# RS232.net
KiCad netlist of a schematic drawn in EasyEDA Pro
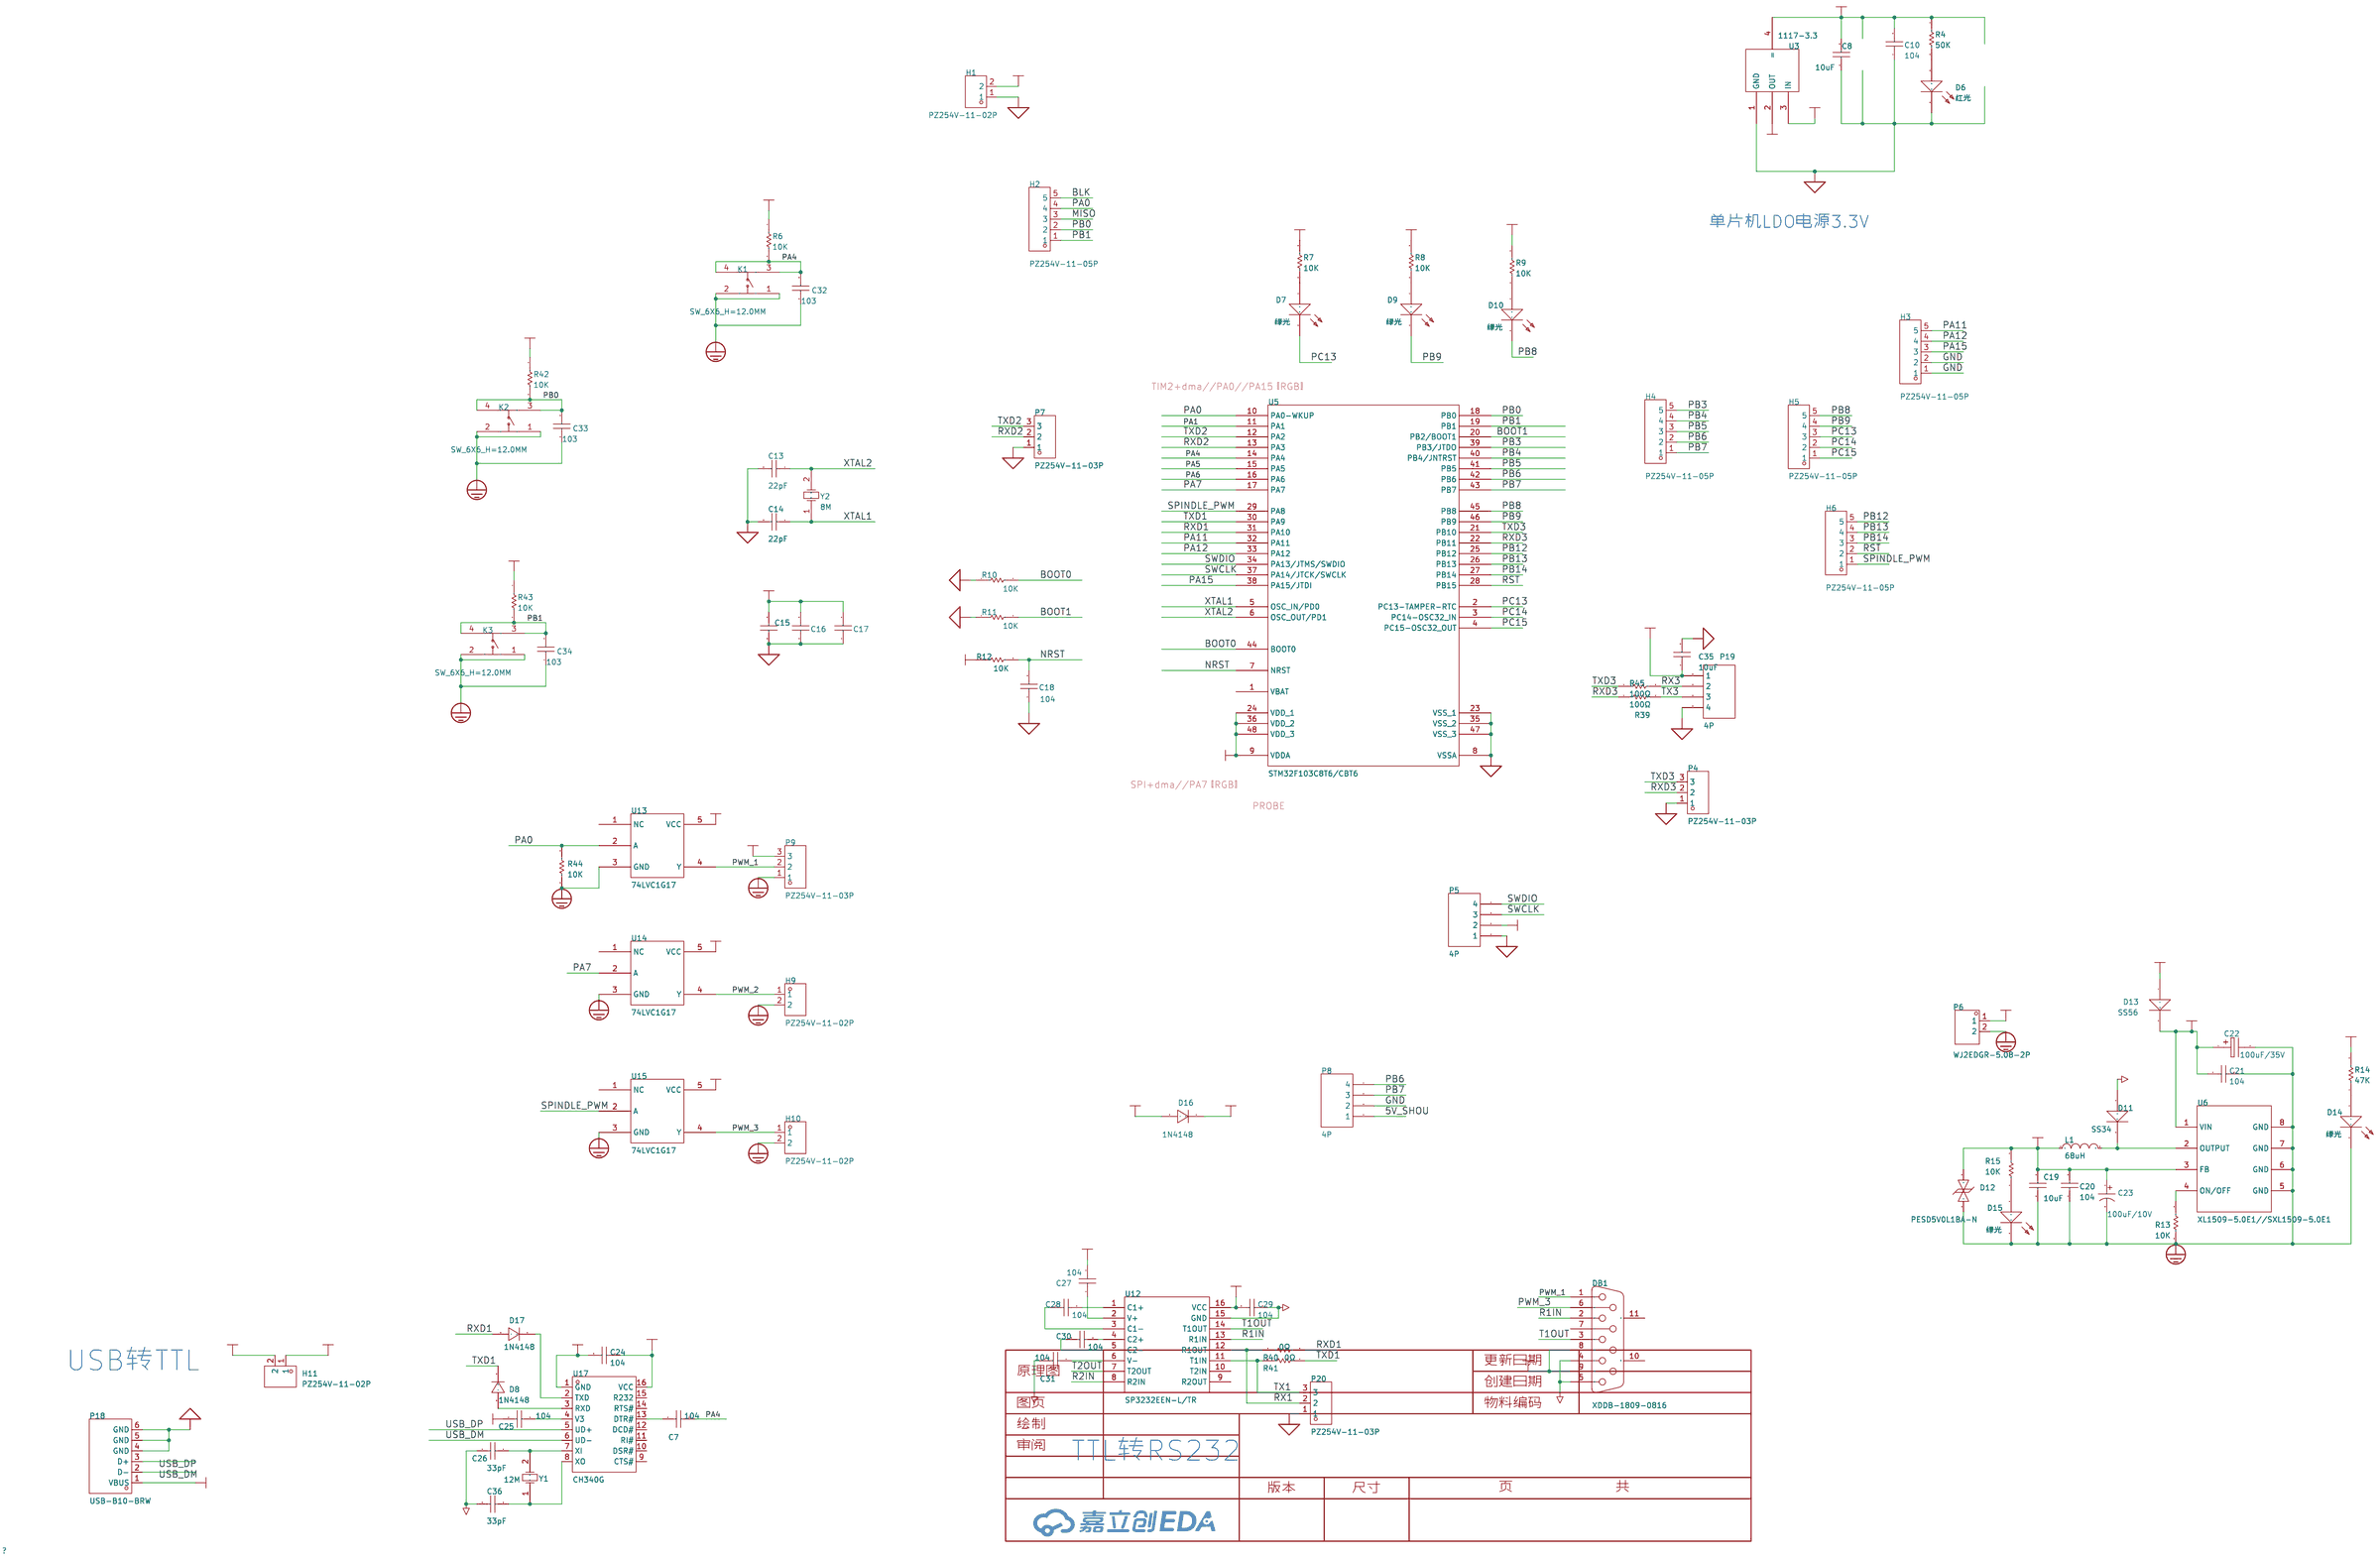
[diagram p0: schematic sheet]

(export (version "E")
  (design (tool "Eeschema 10.0.6"))
  (components
    (comp (ref "C7")
      (value "104")
      (footprint "easyedapro:0603C")
      (description "Capacitor (Semiconductor SIM Model)")
      (libsource (lib "easyedapro") (part "Cap Semi"))
    )
    (comp (ref "C8") (value "10uF") (libsource (lib "") (part "CAP_1")))
    (comp (ref "C10")
      (value "104")
      (footprint "easyedapro:0603C")
      (description "Capacitor (Semiconductor SIM Model)")
      (libsource (lib "easyedapro") (part "Cap Semi"))
    )
    (comp (ref "C13")
      (value "100pF")
      (footprint "easyedapro:0603C")
      (description "Capacitor (Semiconductor SIM Model)")
      (libsource (lib "easyedapro") (part "Cap Semi"))
    )
    (comp (ref "C14")
      (value "100pF")
      (footprint "easyedapro:0603C")
      (description "Capacitor (Semiconductor SIM Model)")
      (libsource (lib "easyedapro") (part "Cap Semi"))
    )
    (comp (ref "C15")
      (value "104")
      (footprint "easyedapro:电解电容贴片6X6")
      (libsource (lib "easyedapro") (part "CAP"))
    )
    (comp (ref "C16")
      (value "104")
      (footprint "easyedapro:电解电容贴片6X6")
      (libsource (lib "easyedapro") (part "CAP"))
    )
    (comp (ref "C17")
      (value "104")
      (footprint "easyedapro:电解电容贴片6X6")
      (libsource (lib "easyedapro") (part "CAP"))
    )
    (comp (ref "C18")
      (value "104")
      (footprint "easyedapro:0603C")
      (description "Capacitor (Semiconductor SIM Model)")
      (libsource (lib "easyedapro") (part "Cap Semi"))
    )
    (comp (ref "C19") (value "10uF") (libsource (lib "") (part "CAP_1")))
    (comp (ref "C20")
      (value "104")
      (footprint "easyedapro:0603C")
      (description "Capacitor (Semiconductor SIM Model)")
      (libsource (lib "easyedapro") (part "Cap Semi"))
    )
    (comp (ref "C21")
      (value "104")
      (footprint "easyedapro:0603C")
      (description "Capacitor (Semiconductor SIM Model)")
      (libsource (lib "easyedapro") (part "Cap Semi"))
    )
    (comp (ref "C22")
      (value "100uF/35V")
      (footprint "easyedapro:电解电容贴片10x10")
      (libsource (lib "easyedapro") (part "ELECTRO1"))
    )
    (comp (ref "C23")
      (value "100uF/10V")
      (footprint "easyedapro:CAP-SMD_BD5.0-L5.3-W5.3-RD")
      (fields (field (name "Manufacturer Part") "CS1A101M-CRD54") (field (name "Manufacturer") "ST(先科)"))
      (libsource (lib "easyedapro") (part "CS1A101M-CRD54"))
    )
    (comp (ref "C24")
      (value "104")
      (footprint "easyedapro:0603C")
      (description "Capacitor (Semiconductor SIM Model)")
      (libsource (lib "easyedapro") (part "Cap Semi"))
    )
    (comp (ref "C25")
      (value "104")
      (footprint "easyedapro:0603C")
      (description "Capacitor (Semiconductor SIM Model)")
      (libsource (lib "easyedapro") (part "Cap Semi"))
    )
    (comp (ref "C26")
      (value "18pF")
      (footprint "easyedapro:0603C")
      (description "Capacitor (Semiconductor SIM Model)")
      (libsource (lib "easyedapro") (part "Cap Semi"))
    )
    (comp (ref "C27")
      (value "104")
      (footprint "easyedapro:0603C")
      (description "Capacitor (Semiconductor SIM Model)")
      (libsource (lib "easyedapro") (part "Cap Semi"))
    )
    (comp (ref "C28")
      (value "104")
      (footprint "easyedapro:0603C")
      (description "Capacitor (Semiconductor SIM Model)")
      (libsource (lib "easyedapro") (part "Cap Semi"))
    )
    (comp (ref "C29")
      (value "104")
      (footprint "easyedapro:0603C")
      (description "Capacitor (Semiconductor SIM Model)")
      (libsource (lib "easyedapro") (part "Cap Semi"))
    )
    (comp (ref "C30")
      (value "104")
      (footprint "easyedapro:0603C")
      (description "Capacitor (Semiconductor SIM Model)")
      (libsource (lib "easyedapro") (part "Cap Semi"))
    )
    (comp (ref "C31")
      (value "104")
      (footprint "easyedapro:0603C")
      (description "Capacitor (Semiconductor SIM Model)")
      (libsource (lib "easyedapro") (part "Cap Semi"))
    )
    (comp (ref "C32") (value "103") (footprint "easyedapro:11") (libsource (lib "easyedapro") (part "CAP")))
    (comp (ref "C33") (value "103") (footprint "easyedapro:11") (libsource (lib "easyedapro") (part "CAP")))
    (comp (ref "C34") (value "103") (footprint "easyedapro:11") (libsource (lib "easyedapro") (part "CAP")))
    (comp (ref "C35") (value "10uF") (libsource (lib "") (part "CAP_1")))
    (comp (ref "C36")
      (value "18pF")
      (footprint "easyedapro:0603C")
      (description "Capacitor (Semiconductor SIM Model)")
      (libsource (lib "easyedapro") (part "Cap Semi"))
    )
    (comp (ref "D6")
      (value "红光")
      (footprint "easyedapro:0603LED")
      (libsource (lib "easyedapro") (part "LED"))
    )
    (comp (ref "D7")
      (value "绿光")
      (footprint "easyedapro:0603LED")
      (libsource (lib "easyedapro") (part "LED"))
    )
    (comp (ref "D8")
      (value "1N4148")
      (footprint "easyedapro:SOD-123_L2.8-W1.8-LS3.7-RD")
      (fields (field (name "Manufacturer") "MCC(美微科)"))
      (libsource (lib "easyedapro") (part "1N4148W-TP"))
    )
    (comp (ref "D9")
      (value "绿光")
      (footprint "easyedapro:0603LED")
      (libsource (lib "easyedapro") (part "LED"))
    )
    (comp (ref "D10")
      (value "绿光")
      (footprint "easyedapro:0603LED")
      (libsource (lib "easyedapro") (part "LED"))
    )
    (comp (ref "D11") (value "SS34") (libsource (lib "easyedapro") (part "1N4148")))
    (comp (ref "D12")
      (value "PESD5V0L1BA-N")
      (footprint "easyedapro:SOD-523_L1.2-W0.8-LS1.6-BI")
      (description "极性:Bidirectional;反向关断电压（典型值）:5V (Max);击穿电压（最小值）:6V;箝位电压:15V;峰值脉冲电流（10/1000us）:5A (8/20us);")
      (fields (field (name "Manufacturer") "BORN伯恩半导体"))
      (libsource (lib "easyedapro") (part "PESD5V0S1BBN"))
    )
    (comp (ref "D13") (value "SS56") (footprint "easyedapro:SMA") (libsource (lib "") (part "1N4148_1")))
    (comp (ref "D14")
      (value "绿光")
      (footprint "easyedapro:0603LED")
      (libsource (lib "easyedapro") (part "LED"))
    )
    (comp (ref "D15")
      (value "绿光")
      (footprint "easyedapro:0603LED")
      (libsource (lib "easyedapro") (part "LED"))
    )
    (comp (ref "D16")
      (value "1N4148")
      (footprint "easyedapro:SOD-123_L2.8-W1.8-LS3.7-RD")
      (fields (field (name "Manufacturer") "MCC(美微科)"))
      (libsource (lib "easyedapro") (part "1N4148W-TP"))
    )
    (comp (ref "D17")
      (value "1N4148")
      (footprint "easyedapro:SOD-123_L2.8-W1.8-LS3.7-RD")
      (fields (field (name "Manufacturer") "MCC(美微科)"))
      (libsource (lib "easyedapro") (part "1N4148W-TP"))
    )
    (comp (ref "DB1")
      (value "XDDB-1809-0816")
      (footprint "easyedapro:DB9-TH_LD09P33E4GV00LF")
      (description "连接器类型:常规D-Sub;公母:公;总PIN位数:9P;安装方式:弯插;排数:2;额定电流-信号脚:3A;工作温度范围:-40°C~+85°C;")
      (fields (field (name "Manufacturer") "LX(连欣科技)"))
      (libsource (lib "easyedapro") (part "XDDB-1809-0816"))
    )
    (comp (ref "H1")
      (value "PZ254V-11-02P")
      (footprint "easyedapro:HDR-TH_2P-P2.54-V-M")
      (fields (field (name "Manufacturer") "XFCN(兴飞)"))
      (libsource (lib "easyedapro") (part "PZ254V-11-02P"))
    )
    (comp (ref "H2")
      (value "PZ254V-11-05P")
      (footprint "easyedapro:HDR-TH_5P-P2.54-V-M")
      (fields (field (name "Manufacturer") "XFCN(兴飞)"))
      (libsource (lib "easyedapro") (part "PZ254V-11-05P"))
    )
    (comp (ref "H3")
      (value "PZ254V-11-05P")
      (footprint "easyedapro:HDR-TH_5P-P2.54-V-M")
      (fields (field (name "Manufacturer") "XFCN(兴飞)"))
      (libsource (lib "easyedapro") (part "PZ254V-11-05P"))
    )
    (comp (ref "H4")
      (value "PZ254V-11-05P")
      (footprint "easyedapro:HDR-TH_5P-P2.54-V-M")
      (fields (field (name "Manufacturer") "XFCN(兴飞)"))
      (libsource (lib "easyedapro") (part "PZ254V-11-05P"))
    )
    (comp (ref "H5")
      (value "PZ254V-11-05P")
      (footprint "easyedapro:HDR-TH_5P-P2.54-V-M")
      (fields (field (name "Manufacturer") "XFCN(兴飞)"))
      (libsource (lib "easyedapro") (part "PZ254V-11-05P"))
    )
    (comp (ref "H6")
      (value "PZ254V-11-05P")
      (footprint "easyedapro:HDR-TH_5P-P2.54-V-M")
      (fields (field (name "Manufacturer") "XFCN(兴飞)"))
      (libsource (lib "easyedapro") (part "PZ254V-11-05P"))
    )
    (comp (ref "H9")
      (value "PZ254V-11-02P")
      (footprint "easyedapro:HDR-TH_2P-P2.54-V-M")
      (fields (field (name "Manufacturer") "XFCN(兴飞)"))
      (libsource (lib "easyedapro") (part "PZ254V-11-02P"))
    )
    (comp (ref "H10")
      (value "PZ254V-11-02P")
      (footprint "easyedapro:HDR-TH_2P-P2.54-V-M")
      (fields (field (name "Manufacturer") "XFCN(兴飞)"))
      (libsource (lib "easyedapro") (part "PZ254V-11-02P"))
    )
    (comp (ref "H11")
      (value "PZ254V-11-02P")
      (footprint "easyedapro:HDR-TH_2P-P2.54-V-M")
      (fields (field (name "Manufacturer") "XFCN(兴飞)"))
      (libsource (lib "easyedapro") (part "PZ254V-11-02P"))
    )
    (comp (ref "K1")
      (value "SW_6X6_H=12.0MM")
      (footprint "easyedapro:KEY-SMD_4P-L6.0-W6.0-P4.50-LS9.0")
      (libsource (lib "easyedapro") (part "SW_6X6_H=12.0MM"))
    )
    (comp (ref "K2")
      (value "SW_6X6_H=12.0MM")
      (footprint "easyedapro:KEY-SMD_4P-L6.0-W6.0-P4.50-LS9.0")
      (libsource (lib "easyedapro") (part "SW_6X6_H=12.0MM"))
    )
    (comp (ref "K3")
      (value "SW_6X6_H=12.0MM")
      (footprint "easyedapro:KEY-SMD_4P-L6.0-W6.0-P4.50-LS9.0")
      (libsource (lib "easyedapro") (part "SW_6X6_H=12.0MM"))
    )
    (comp (ref "L1")
      (value "68uH")
      (footprint "easyedapro:IND-SMD_L7.0-W7.0_SMDRI74-330MT")
      (description "电感值:33uH;精度:±20%;额定电流:960mA;饱和电流(Isat):1.8A;类型:屏蔽电感;")
      (fields (field (name "Manufacturer Part") "SMDRI74-330MT") (field (name "Manufacturer") "SXN(顺翔诺)"))
      (libsource (lib "easyedapro") (part "SMDRI74-330MT"))
    )
    (comp (ref "P4")
      (value "PZ254V-11-03P")
      (footprint "easyedapro:HDR-TH_3P-P2.54-V-M")
      (fields (field (name "Manufacturer") "XFCN(兴飞)"))
      (libsource (lib "easyedapro") (part "PZ254V-11-03P_C2937625"))
    )
    (comp (ref "P5") (value "4P") (libsource (lib "easyedapro") (part "4P")))
    (comp (ref "P6")
      (value "WJ2EDGR-5.08-2P")
      (footprint "easyedapro:CONN-TH_WJ2EDGR-5.08-2P")
      (description "每排PIN数:2;安装方式:弯针;排数:1;间距:5.08mm;连接器类型:板端/插座-开口;")
      (fields (field (name "Manufacturer") "KANGNEX(康奈克斯电气)"))
      (libsource (lib "easyedapro") (part "WJ2EDGR-5.08-2P"))
    )
    (comp (ref "P7")
      (value "PZ254V-11-03P")
      (footprint "easyedapro:HDR-TH_3P-P2.54-V-M")
      (fields (field (name "Manufacturer") "XFCN(兴飞)"))
      (libsource (lib "easyedapro") (part "PZ254V-11-03P_C2937625"))
    )
    (comp (ref "P8") (value "4P") (libsource (lib "easyedapro") (part "4P")))
    (comp (ref "P9")
      (value "PZ254V-11-03P")
      (footprint "easyedapro:HDR-TH_3P-P2.54-V-M")
      (fields (field (name "Manufacturer") "XFCN(兴飞)"))
      (libsource (lib "easyedapro") (part "PZ254V-11-03P_C2937625"))
    )
    (comp (ref "P18")
      (value "USB-B10-BRW")
      (footprint "easyedapro:USB-B-TH_USB-B10-BRW")
      (fields (field (name "Manufacturer") "XUNPU(讯普)"))
      (libsource (lib "easyedapro") (part "USB-B10-BRW"))
    )
    (comp (ref "P19") (value "4P") (footprint "easyedapro:HDR1X4_CON") (libsource (lib "") (part "4P_1")))
    (comp (ref "P20")
      (value "PZ254V-11-03P")
      (footprint "easyedapro:HDR-TH_3P-P2.54-V-M")
      (fields (field (name "Manufacturer") "XFCN(兴飞)"))
      (libsource (lib "easyedapro") (part "PZ254V-11-03P_C2937625"))
    )
    (comp (ref "R4")
      (value "50K")
      (footprint "easyedapro:0603R")
      (description "Resistor")
      (libsource (lib "easyedapro") (part "RES"))
    )
    (comp (ref "R6")
      (value "10K")
      (footprint "easyedapro:0603R")
      (description "Resistor")
      (libsource (lib "easyedapro") (part "RES"))
    )
    (comp (ref "R7")
      (value "10K")
      (footprint "easyedapro:0603R")
      (description "Resistor")
      (libsource (lib "easyedapro") (part "RES"))
    )
    (comp (ref "R8")
      (value "10K")
      (footprint "easyedapro:0603R")
      (description "Resistor")
      (libsource (lib "easyedapro") (part "RES"))
    )
    (comp (ref "R9")
      (value "10K")
      (footprint "easyedapro:0603R")
      (description "Resistor")
      (libsource (lib "easyedapro") (part "RES"))
    )
    (comp (ref "R10")
      (value "10K")
      (footprint "easyedapro:0603R")
      (description "Resistor")
      (libsource (lib "easyedapro") (part "RES"))
    )
    (comp (ref "R11")
      (value "10K")
      (footprint "easyedapro:0603R")
      (description "Resistor")
      (libsource (lib "easyedapro") (part "RES"))
    )
    (comp (ref "R12")
      (value "10K")
      (footprint "easyedapro:0603R")
      (description "Resistor")
      (libsource (lib "easyedapro") (part "RES"))
    )
    (comp (ref "R13")
      (value "10K")
      (footprint "easyedapro:0603R")
      (description "Resistor")
      (libsource (lib "easyedapro") (part "RES"))
    )
    (comp (ref "R14")
      (value "47K")
      (footprint "easyedapro:0603R")
      (description "Resistor")
      (libsource (lib "easyedapro") (part "RES"))
    )
    (comp (ref "R15")
      (value "10K")
      (footprint "easyedapro:0603R")
      (description "Resistor")
      (libsource (lib "easyedapro") (part "RES"))
    )
    (comp (ref "R39")
      (value "100Ω")
      (description "Resistor")
      (fields (field (name "Publisher") "Altium Limited"))
      (libsource (lib "") (part "RES_1"))
    )
    (comp (ref "R40")
      (value "0Ω")
      (footprint "easyedapro:0603R")
      (description "Resistor")
      (libsource (lib "easyedapro") (part "RES"))
    )
    (comp (ref "R41")
      (value "0Ω")
      (footprint "easyedapro:0603R")
      (description "Resistor")
      (libsource (lib "easyedapro") (part "RES"))
    )
    (comp (ref "R42")
      (value "10K")
      (footprint "easyedapro:0603R")
      (description "Resistor")
      (libsource (lib "easyedapro") (part "RES"))
    )
    (comp (ref "R43")
      (value "10K")
      (footprint "easyedapro:0603R")
      (description "Resistor")
      (libsource (lib "easyedapro") (part "RES"))
    )
    (comp (ref "R44")
      (value "10K")
      (footprint "easyedapro:0603R")
      (description "Resistor")
      (libsource (lib "easyedapro") (part "RES"))
    )
    (comp (ref "R45")
      (value "100Ω")
      (description "Resistor")
      (fields (field (name "Publisher") "Altium Limited"))
      (libsource (lib "") (part "RES_1"))
    )
    (comp (ref "U3")
      (value "1117-3.3")
      (footprint "easyedapro:SOT-223")
      (libsource (lib "easyedapro") (part "LM1117"))
    )
    (comp (ref "U5")
      (value "STM32F103C8T6/CBT6")
      (footprint "easyedapro:LQFP48")
      (description "STM32 ARM-based 32-bit MCU with 32 Kbytes Flash, 48-pin LQFP, Industrial Temperature")
      (libsource (lib "easyedapro") (part "STM32F103C6T6"))
    )
    (comp (ref "U6")
      (value "XL1509-5.0E1//SXL1509-5.0E1")
      (footprint "easyedapro:SOIC-8_L5.0-W4.0-P1.27-LS6.0-BL")
      (description "功能类型:降压型;同步整流:-;输出通道数:-;拓扑结构:-;输入电压:-;输出电流(最大值):-;开关频率:-;")
      (fields (field (name "Manufacturer") "XLSEMI(芯龙)"))
      (libsource (lib "easyedapro") (part "XL1509-5.0E1"))
    )
    (comp (ref "U12")
      (value "SP3232EEN-L/TR")
      (footprint "easyedapro:SOIC-16_L9.9-W3.9-P1.27-LS6.0-BL")
      (description "类型:收发器;数据速率:235Kbps;")
      (fields (field (name "Manufacturer") "MaxLinear(迈凌)"))
      (libsource (lib "easyedapro") (part "SP3232EEN-L/TR"))
    )
    (comp (ref "U13")
      (value "74LVC1G17")
      (footprint "easyedapro:SMD8")
      (libsource (lib "easyedapro") (part "74LVC1G04"))
    )
    (comp (ref "U14")
      (value "74LVC1G17")
      (footprint "easyedapro:SMD8")
      (libsource (lib "easyedapro") (part "74LVC1G04"))
    )
    (comp (ref "U15")
      (value "74LVC1G17")
      (footprint "easyedapro:SMD8")
      (libsource (lib "easyedapro") (part "74LVC1G04"))
    )
    (comp (ref "U17")
      (value "CH340G")
      (footprint "easyedapro:SOIC-16_L9.9-W3.9-P1.27-LS6.0-BL")
      (description "应用功能:收发器;接口协议:USB 2.0;数据速率:2Mbps;")
      (fields (field (name "Manufacturer") "WCH(南京沁恒)"))
      (libsource (lib "easyedapro") (part "CH340G"))
    )
    (comp (ref "Y1")
      (value "12M")
      (footprint "easyedapro:晶振贴片49SSMD")
      (description "Crystal Oscillator")
      (libsource (lib "easyedapro") (part "XTAL"))
    )
    (comp (ref "Y2")
      (value "8M")
      (footprint "easyedapro:晶振贴片49SSMD")
      (description "Crystal Oscillator")
      (libsource (lib "easyedapro") (part "XTAL"))
    )
  )
  (nets
    (net (code "1") (name "/BLK") (class "Default")
      (node (ref "H2") (pin "5") (pinfunction "5_5") (pintype "input"))
    )
    (net (code "2") (name "/BOOT0") (class "Default")
      (node (ref "R10") (pin "2") (pinfunction "2_2") (pintype "unspecified"))
      (node (ref "U5") (pin "44") (pinfunction "BOOT0_44") (pintype "input"))
    )
    (net (code "3") (name "/BOOT1") (class "Default")
      (node (ref "R11") (pin "2") (pinfunction "2_2") (pintype "unspecified"))
      (node (ref "U5") (pin "20") (pinfunction "PB2/BOOT1_20") (pintype "bidirectional"))
    )
    (net (code "4") (name "/MISO") (class "Default")
      (node (ref "H2") (pin "3") (pinfunction "3_3") (pintype "input"))
    )
    (net (code "5") (name "/NRST") (class "Default")
      (node (ref "C18") (pin "2") (pinfunction "2_2") (pintype "unspecified"))
      (node (ref "R12") (pin "2") (pinfunction "2_2") (pintype "unspecified"))
      (node (ref "U5") (pin "7") (pinfunction "NRST_7") (pintype "bidirectional"))
    )
    (net (code "6") (name "/PA0") (class "Default")
      (node (ref "H2") (pin "4") (pinfunction "4_4") (pintype "input"))
      (node (ref "R44") (pin "2") (pinfunction "2_2") (pintype "unspecified"))
      (node (ref "U13") (pin "2") (pinfunction "A_2") (pintype "unspecified"))
      (node (ref "U5") (pin "10") (pinfunction "PA0-WKUP_10") (pintype "bidirectional"))
    )
    (net (code "7") (name "/PA1") (class "Default")
      (node (ref "U5") (pin "11") (pinfunction "PA1_11") (pintype "bidirectional"))
    )
    (net (code "8") (name "/PA4") (class "Default")
      (node (ref "C32") (pin "2") (pinfunction "2_2") (pintype "unspecified"))
      (node (ref "C7") (pin "2") (pinfunction "2_2") (pintype "unspecified"))
      (node (ref "K1") (pin "3") (pinfunction "3_3") (pintype "unspecified"))
      (node (ref "K1") (pin "4") (pinfunction "4_4") (pintype "unspecified"))
      (node (ref "R6") (pin "2") (pinfunction "2_2") (pintype "unspecified"))
      (node (ref "U5") (pin "14") (pinfunction "PA4_14") (pintype "bidirectional"))
    )
    (net (code "9") (name "/PA5") (class "Default")
      (node (ref "U5") (pin "15") (pinfunction "PA5_15") (pintype "bidirectional"))
    )
    (net (code "10") (name "/PA6") (class "Default")
      (node (ref "U5") (pin "16") (pinfunction "PA6_16") (pintype "bidirectional"))
    )
    (net (code "11") (name "/PA7") (class "Default")
      (node (ref "U14") (pin "2") (pinfunction "A_2") (pintype "unspecified"))
      (node (ref "U5") (pin "17") (pinfunction "PA7_17") (pintype "bidirectional"))
    )
    (net (code "12") (name "/PA11") (class "Default")
      (node (ref "H3") (pin "5") (pinfunction "5_5") (pintype "input"))
      (node (ref "U5") (pin "32") (pinfunction "PA11_32") (pintype "bidirectional"))
    )
    (net (code "13") (name "/PA12") (class "Default")
      (node (ref "H3") (pin "4") (pinfunction "4_4") (pintype "input"))
      (node (ref "U5") (pin "33") (pinfunction "PA12_33") (pintype "bidirectional"))
    )
    (net (code "14") (name "/PA15") (class "Default")
      (node (ref "H3") (pin "3") (pinfunction "3_3") (pintype "input"))
      (node (ref "U5") (pin "38") (pinfunction "PA15/JTDI_38") (pintype "bidirectional"))
    )
    (net (code "15") (name "/PB0") (class "Default")
      (node (ref "C33") (pin "2") (pinfunction "2_2") (pintype "unspecified"))
      (node (ref "H2") (pin "2") (pinfunction "2_2") (pintype "input"))
      (node (ref "K2") (pin "3") (pinfunction "3_3") (pintype "unspecified"))
      (node (ref "K2") (pin "4") (pinfunction "4_4") (pintype "unspecified"))
      (node (ref "R42") (pin "2") (pinfunction "2_2") (pintype "unspecified"))
      (node (ref "U5") (pin "18") (pinfunction "PB0_18") (pintype "bidirectional"))
    )
    (net (code "16") (name "/PB1") (class "Default")
      (node (ref "C34") (pin "2") (pinfunction "2_2") (pintype "unspecified"))
      (node (ref "H2") (pin "1") (pinfunction "1_1") (pintype "input"))
      (node (ref "K3") (pin "3") (pinfunction "3_3") (pintype "unspecified"))
      (node (ref "K3") (pin "4") (pinfunction "4_4") (pintype "unspecified"))
      (node (ref "R43") (pin "2") (pinfunction "2_2") (pintype "unspecified"))
      (node (ref "U5") (pin "19") (pinfunction "PB1_19") (pintype "bidirectional"))
    )
    (net (code "17") (name "/PB3") (class "Default")
      (node (ref "H4") (pin "5") (pinfunction "5_5") (pintype "input"))
      (node (ref "U5") (pin "39") (pinfunction "PB3/JTDO_39") (pintype "bidirectional"))
    )
    (net (code "18") (name "/PB4") (class "Default")
      (node (ref "H4") (pin "4") (pinfunction "4_4") (pintype "input"))
      (node (ref "U5") (pin "40") (pinfunction "PB4/JNTRST_40") (pintype "bidirectional"))
    )
    (net (code "19") (name "/PB5") (class "Default")
      (node (ref "H4") (pin "3") (pinfunction "3_3") (pintype "input"))
      (node (ref "U5") (pin "41") (pinfunction "PB5_41") (pintype "bidirectional"))
    )
    (net (code "20") (name "/PB6") (class "Default")
      (node (ref "H4") (pin "2") (pinfunction "2_2") (pintype "input"))
      (node (ref "P8") (pin "4") (pinfunction "4_4") (pintype "input"))
      (node (ref "U5") (pin "42") (pinfunction "PB6_42") (pintype "bidirectional"))
    )
    (net (code "21") (name "/PB7") (class "Default")
      (node (ref "H4") (pin "1") (pinfunction "1_1") (pintype "input"))
      (node (ref "P8") (pin "3") (pinfunction "3_3") (pintype "input"))
      (node (ref "U5") (pin "43") (pinfunction "PB7_43") (pintype "bidirectional"))
    )
    (net (code "22") (name "/PB8") (class "Default")
      (node (ref "D10") (pin "2") (pinfunction "2_2") (pintype "unspecified"))
      (node (ref "H5") (pin "5") (pinfunction "5_5") (pintype "input"))
      (node (ref "U5") (pin "45") (pinfunction "PB8_45") (pintype "bidirectional"))
    )
    (net (code "23") (name "/PB9") (class "Default")
      (node (ref "D9") (pin "2") (pinfunction "2_2") (pintype "unspecified"))
      (node (ref "H5") (pin "4") (pinfunction "4_4") (pintype "input"))
      (node (ref "U5") (pin "46") (pinfunction "PB9_46") (pintype "bidirectional"))
    )
    (net (code "24") (name "/PB12") (class "Default")
      (node (ref "H6") (pin "5") (pinfunction "5_5") (pintype "input"))
      (node (ref "U5") (pin "25") (pinfunction "PB12_25") (pintype "bidirectional"))
    )
    (net (code "25") (name "/PB13") (class "Default")
      (node (ref "H6") (pin "4") (pinfunction "4_4") (pintype "input"))
      (node (ref "U5") (pin "26") (pinfunction "PB13_26") (pintype "bidirectional"))
    )
    (net (code "26") (name "/PB14") (class "Default")
      (node (ref "H6") (pin "3") (pinfunction "3_3") (pintype "input"))
      (node (ref "U5") (pin "27") (pinfunction "PB14_27") (pintype "bidirectional"))
    )
    (net (code "27") (name "/PC13") (class "Default")
      (node (ref "D7") (pin "2") (pinfunction "2_2") (pintype "unspecified"))
      (node (ref "H5") (pin "3") (pinfunction "3_3") (pintype "input"))
      (node (ref "U5") (pin "2") (pinfunction "PC13-TAMPER-RTC_2") (pintype "bidirectional"))
    )
    (net (code "28") (name "/PC14") (class "Default")
      (node (ref "H5") (pin "2") (pinfunction "2_2") (pintype "input"))
      (node (ref "U5") (pin "3") (pinfunction "PC14-OSC32_IN_3") (pintype "bidirectional"))
    )
    (net (code "29") (name "/PC15") (class "Default")
      (node (ref "H5") (pin "1") (pinfunction "1_1") (pintype "input"))
      (node (ref "U5") (pin "4") (pinfunction "PC15-OSC32_OUT_4") (pintype "bidirectional"))
    )
    (net (code "30") (name "/PWM_1") (class "Default")
      (node (ref "DB1") (pin "1") (pinfunction "1_1") (pintype "input"))
      (node (ref "P9") (pin "2") (pinfunction "2_2") (pintype "unspecified"))
      (node (ref "U13") (pin "4") (pinfunction "Y_4") (pintype "unspecified"))
    )
    (net (code "31") (name "/PWM_2") (class "Default")
      (node (ref "H9") (pin "1") (pinfunction "1_1") (pintype "unspecified"))
      (node (ref "U14") (pin "4") (pinfunction "Y_4") (pintype "unspecified"))
    )
    (net (code "32") (name "/PWM_3") (class "Default")
      (node (ref "DB1") (pin "6") (pinfunction "6_6") (pintype "input"))
      (node (ref "H10") (pin "1") (pinfunction "1_1") (pintype "unspecified"))
      (node (ref "U15") (pin "4") (pinfunction "Y_4") (pintype "unspecified"))
    )
    (net (code "33") (name "/R1IN") (class "Default")
      (node (ref "DB1") (pin "2") (pinfunction "2_2") (pintype "input"))
      (node (ref "U12") (pin "13") (pinfunction "R1IN_13") (pintype "unspecified"))
    )
    (net (code "34") (name "/R2IN") (class "Default")
      (node (ref "U12") (pin "8") (pinfunction "R2IN_8") (pintype "unspecified"))
    )
    (net (code "35") (name "/RST") (class "Default")
      (node (ref "H6") (pin "2") (pinfunction "2_2") (pintype "input"))
      (node (ref "U5") (pin "28") (pinfunction "PB15_28") (pintype "bidirectional"))
    )
    (net (code "36") (name "/RX1") (class "Default")
      (node (ref "P20") (pin "2") (pinfunction "2_2") (pintype "unspecified"))
      (node (ref "R40") (pin "2") (pinfunction "2_2") (pintype "unspecified"))
      (node (ref "U12") (pin "12") (pinfunction "R1OUT_12") (pintype "unspecified"))
    )
    (net (code "37") (name "/RX3") (class "Default")
      (node (ref "P19") (pin "2") (pinfunction "2_2") (pintype "unspecified"))
      (node (ref "R45") (pin "2") (pinfunction "2_2") (pintype "input"))
    )
    (net (code "38") (name "/RXD1") (class "Default")
      (node (ref "D17") (pin "2") (pinfunction "A_2") (pintype "input"))
      (node (ref "R40") (pin "1") (pinfunction "1_1") (pintype "unspecified"))
      (node (ref "U5") (pin "31") (pinfunction "PA10_31") (pintype "bidirectional"))
    )
    (net (code "39") (name "/RXD2") (class "Default")
      (node (ref "P7") (pin "2") (pinfunction "2_2") (pintype "unspecified"))
      (node (ref "U5") (pin "13") (pinfunction "PA3_13") (pintype "bidirectional"))
    )
    (net (code "40") (name "/RXD3") (class "Default")
      (node (ref "P4") (pin "2") (pinfunction "2_2") (pintype "unspecified"))
      (node (ref "R39") (pin "1") (pinfunction "1_1") (pintype "input"))
      (node (ref "U5") (pin "22") (pinfunction "PB11_22") (pintype "bidirectional"))
    )
    (net (code "41") (name "/SPINDLE_PWM") (class "Default")
      (node (ref "H6") (pin "1") (pinfunction "1_1") (pintype "input"))
      (node (ref "U15") (pin "2") (pinfunction "A_2") (pintype "unspecified"))
      (node (ref "U5") (pin "29") (pinfunction "PA8_29") (pintype "bidirectional"))
    )
    (net (code "42") (name "/SWCLK") (class "Default")
      (node (ref "P5") (pin "3") (pinfunction "3_3") (pintype "input"))
      (node (ref "U5") (pin "37") (pinfunction "PA14/JTCK/SWCLK_37") (pintype "bidirectional"))
    )
    (net (code "43") (name "/SWDIO") (class "Default")
      (node (ref "P5") (pin "4") (pinfunction "4_4") (pintype "input"))
      (node (ref "U5") (pin "34") (pinfunction "PA13/JTMS/SWDIO_34") (pintype "bidirectional"))
    )
    (net (code "44") (name "/T1OUT") (class "Default")
      (node (ref "DB1") (pin "3") (pinfunction "3_3") (pintype "input"))
      (node (ref "U12") (pin "14") (pinfunction "T1OUT_14") (pintype "unspecified"))
    )
    (net (code "45") (name "/T2OUT") (class "Default")
      (node (ref "U12") (pin "7") (pinfunction "T2OUT_7") (pintype "unspecified"))
    )
    (net (code "46") (name "/TX1") (class "Default")
      (node (ref "P20") (pin "3") (pinfunction "3_3") (pintype "unspecified"))
      (node (ref "R41") (pin "2") (pinfunction "2_2") (pintype "unspecified"))
      (node (ref "U12") (pin "11") (pinfunction "T1IN_11") (pintype "unspecified"))
    )
    (net (code "47") (name "/TX3") (class "Default")
      (node (ref "P19") (pin "3") (pinfunction "3_3") (pintype "unspecified"))
      (node (ref "R39") (pin "2") (pinfunction "2_2") (pintype "input"))
    )
    (net (code "48") (name "/TXD1") (class "Default")
      (node (ref "D8") (pin "1") (pinfunction "c_1") (pintype "input"))
      (node (ref "R41") (pin "1") (pinfunction "1_1") (pintype "unspecified"))
      (node (ref "U5") (pin "30") (pinfunction "PA9_30") (pintype "bidirectional"))
    )
    (net (code "49") (name "/TXD2") (class "Default")
      (node (ref "P7") (pin "3") (pinfunction "3_3") (pintype "unspecified"))
      (node (ref "U5") (pin "12") (pinfunction "PA2_12") (pintype "bidirectional"))
    )
    (net (code "50") (name "/TXD3") (class "Default")
      (node (ref "P4") (pin "3") (pinfunction "3_3") (pintype "unspecified"))
      (node (ref "R45") (pin "1") (pinfunction "1_1") (pintype "input"))
      (node (ref "U5") (pin "21") (pinfunction "PB10_21") (pintype "bidirectional"))
    )
    (net (code "51") (name "/USB_DM") (class "Default")
      (node (ref "P18") (pin "2") (pinfunction "D-_2") (pintype "unspecified"))
      (node (ref "U17") (pin "6") (pinfunction "UD-_6") (pintype "unspecified"))
    )
    (net (code "52") (name "/USB_DP") (class "Default")
      (node (ref "P18") (pin "3") (pinfunction "D+_3") (pintype "unspecified"))
      (node (ref "U17") (pin "5") (pinfunction "UD+_5") (pintype "unspecified"))
    )
    (net (code "53") (name "/XTAL1") (class "Default")
      (node (ref "C14") (pin "1") (pinfunction "1_1") (pintype "unspecified"))
      (node (ref "U5") (pin "5") (pinfunction "OSC_IN/PD0_5") (pintype "input"))
      (node (ref "Y2") (pin "1") (pinfunction "OSC1_1") (pintype "unspecified"))
    )
    (net (code "54") (name "/XTAL2") (class "Default")
      (node (ref "C13") (pin "1") (pinfunction "1_1") (pintype "unspecified"))
      (node (ref "U5") (pin "6") (pinfunction "OSC_OUT/PD1_6") (pintype "output"))
      (node (ref "Y2") (pin "2") (pinfunction "OSC2_2") (pintype "unspecified"))
    )
    (net (code "55") (name "3V3") (class "Default")
      (node (ref "C10") (pin "2") (pinfunction "2_2") (pintype "unspecified"))
      (node (ref "C15") (pin "2") (pinfunction "2_2") (pintype "unspecified"))
      (node (ref "C16") (pin "2") (pinfunction "2_2") (pintype "unspecified"))
      (node (ref "C17") (pin "2") (pinfunction "2_2") (pintype "unspecified"))
      (node (ref "C8") (pin "2") (pinfunction "2_2") (pintype "input"))
      (node (ref "P5") (pin "2") (pinfunction "2_2") (pintype "input"))
      (node (ref "R12") (pin "1") (pinfunction "1_1") (pintype "unspecified"))
      (node (ref "R4") (pin "1") (pinfunction "1_1") (pintype "unspecified"))
      (node (ref "R42") (pin "1") (pinfunction "1_1") (pintype "unspecified"))
      (node (ref "R43") (pin "1") (pinfunction "1_1") (pintype "unspecified"))
      (node (ref "R6") (pin "1") (pinfunction "1_1") (pintype "unspecified"))
      (node (ref "R7") (pin "2") (pinfunction "2_2") (pintype "unspecified"))
      (node (ref "R8") (pin "2") (pinfunction "2_2") (pintype "unspecified"))
      (node (ref "R9") (pin "2") (pinfunction "2_2") (pintype "unspecified"))
      (node (ref "U3") (pin "2") (pinfunction "OUT_2") (pintype "unspecified"))
      (node (ref "U3") (pin "4") (pinfunction "=_4") (pintype "unspecified"))
      (node (ref "U5") (pin "24") (pinfunction "VDD_1_24") (pintype "unspecified"))
      (node (ref "U5") (pin "36") (pinfunction "VDD_2_36") (pintype "unspecified"))
      (node (ref "U5") (pin "48") (pinfunction "VDD_3_48") (pintype "unspecified"))
      (node (ref "U5") (pin "9") (pinfunction "VDDA_9") (pintype "unspecified"))
    )
    (net (code "56") (name "5V_SHOU") (class "Default")
      (node (ref "D16") (pin "1") (pinfunction "c_1") (pintype "input"))
      (node (ref "P8") (pin "1") (pinfunction "1_1") (pintype "input"))
    )
    (net (code "57") (name "5V_VCC") (class "Default")
      (node (ref "C19") (pin "1") (pinfunction "1_1") (pintype "input"))
      (node (ref "C20") (pin "2") (pinfunction "2_2") (pintype "unspecified"))
      (node (ref "C23") (pin "1") (pinfunction "1_1") (pintype "input"))
      (node (ref "C24") (pin "1") (pinfunction "1_1") (pintype "unspecified"))
      (node (ref "C27") (pin "1") (pinfunction "1_1") (pintype "unspecified"))
      (node (ref "C29") (pin "2") (pinfunction "2_2") (pintype "unspecified"))
      (node (ref "C35") (pin "1") (pinfunction "1_1") (pintype "input"))
      (node (ref "D12") (pin "2") (pinfunction "2_2") (pintype "input"))
      (node (ref "D16") (pin "2") (pinfunction "A_2") (pintype "input"))
      (node (ref "H1") (pin "2") (pinfunction "2_2") (pintype "unspecified"))
      (node (ref "H11") (pin "1") (pinfunction "1_1") (pintype "unspecified"))
      (node (ref "L1") (pin "1") (pinfunction "1_1") (pintype "unspecified"))
      (node (ref "P19") (pin "1") (pinfunction "1_1") (pintype "unspecified"))
      (node (ref "P9") (pin "3") (pinfunction "3_3") (pintype "unspecified"))
      (node (ref "R15") (pin "2") (pinfunction "2_2") (pintype "unspecified"))
      (node (ref "U12") (pin "16") (pinfunction "VCC_16") (pintype "unspecified"))
      (node (ref "U13") (pin "5") (pinfunction "VCC_5") (pintype "unspecified"))
      (node (ref "U14") (pin "5") (pinfunction "VCC_5") (pintype "unspecified"))
      (node (ref "U15") (pin "5") (pinfunction "VCC_5") (pintype "unspecified"))
      (node (ref "U17") (pin "16") (pinfunction "VCC_16") (pintype "unspecified"))
      (node (ref "U3") (pin "3") (pinfunction "IN_3") (pintype "unspecified"))
      (node (ref "U6") (pin "3") (pinfunction "FB_3") (pintype "input"))
    )
    (net (code "58") (name "24V") (class "Default")
      (node (ref "D13") (pin "1") (pinfunction "1_1") (pintype "unspecified"))
      (node (ref "DB1") (pin "8") (pinfunction "8_8") (pintype "input"))
      (node (ref "DB1") (pin "9") (pinfunction "9_9") (pintype "input"))
      (node (ref "P6") (pin "1") (pinfunction "1_1") (pintype "input"))
      (node (ref "R14") (pin "2") (pinfunction "2_2") (pintype "unspecified"))
    )
    (net (code "59") (name "GND") (class "Default")
      (node (ref "C10") (pin "1") (pinfunction "1_1") (pintype "unspecified"))
      (node (ref "C13") (pin "2") (pinfunction "2_2") (pintype "unspecified"))
      (node (ref "C14") (pin "2") (pinfunction "2_2") (pintype "unspecified"))
      (node (ref "C15") (pin "1") (pinfunction "1_1") (pintype "unspecified"))
      (node (ref "C16") (pin "1") (pinfunction "1_1") (pintype "unspecified"))
      (node (ref "C17") (pin "1") (pinfunction "1_1") (pintype "unspecified"))
      (node (ref "C18") (pin "1") (pinfunction "1_1") (pintype "unspecified"))
      (node (ref "C19") (pin "2") (pinfunction "2_2") (pintype "input"))
      (node (ref "C20") (pin "1") (pinfunction "1_1") (pintype "unspecified"))
      (node (ref "C21") (pin "1") (pinfunction "1_1") (pintype "unspecified"))
      (node (ref "C22") (pin "2") (pintype "unspecified"))
      (node (ref "C23") (pin "2") (pinfunction "2_2") (pintype "input"))
      (node (ref "C24") (pin "2") (pinfunction "2_2") (pintype "unspecified"))
      (node (ref "C25") (pin "2") (pinfunction "2_2") (pintype "unspecified"))
      (node (ref "C26") (pin "2") (pinfunction "2_2") (pintype "unspecified"))
      (node (ref "C29") (pin "1") (pinfunction "1_1") (pintype "unspecified"))
      (node (ref "C31") (pin "2") (pinfunction "2_2") (pintype "unspecified"))
      (node (ref "C32") (pin "1") (pinfunction "1_1") (pintype "unspecified"))
      (node (ref "C33") (pin "1") (pinfunction "1_1") (pintype "unspecified"))
      (node (ref "C34") (pin "1") (pinfunction "1_1") (pintype "unspecified"))
      (node (ref "C35") (pin "2") (pinfunction "2_2") (pintype "input"))
      (node (ref "C36") (pin "2") (pinfunction "2_2") (pintype "unspecified"))
      (node (ref "C8") (pin "1") (pinfunction "1_1") (pintype "input"))
      (node (ref "D11") (pin "1") (pinfunction "1_1") (pintype "input"))
      (node (ref "D12") (pin "1") (pinfunction "1_1") (pintype "input"))
      (node (ref "D14") (pin "2") (pinfunction "2_2") (pintype "unspecified"))
      (node (ref "D15") (pin "2") (pinfunction "2_2") (pintype "unspecified"))
      (node (ref "D6") (pin "2") (pinfunction "2_2") (pintype "unspecified"))
      (node (ref "DB1") (pin "4") (pinfunction "4_4") (pintype "input"))
      (node (ref "DB1") (pin "5") (pinfunction "5_5") (pintype "input"))
      (node (ref "H1") (pin "1") (pinfunction "1_1") (pintype "unspecified"))
      (node (ref "H10") (pin "2") (pinfunction "2_2") (pintype "unspecified"))
      (node (ref "H3") (pin "1") (pinfunction "1_1") (pintype "input"))
      (node (ref "H3") (pin "2") (pinfunction "2_2") (pintype "input"))
      (node (ref "H9") (pin "2") (pinfunction "2_2") (pintype "unspecified"))
      (node (ref "K1") (pin "1") (pinfunction "1_1") (pintype "unspecified"))
      (node (ref "K1") (pin "2") (pinfunction "2_2") (pintype "unspecified"))
      (node (ref "K2") (pin "1") (pinfunction "1_1") (pintype "unspecified"))
      (node (ref "K2") (pin "2") (pinfunction "2_2") (pintype "unspecified"))
      (node (ref "K3") (pin "1") (pinfunction "1_1") (pintype "unspecified"))
      (node (ref "K3") (pin "2") (pinfunction "2_2") (pintype "unspecified"))
      (node (ref "P18") (pin "4") (pinfunction "GND_4") (pintype "unspecified"))
      (node (ref "P18") (pin "5") (pinfunction "GND_5") (pintype "unspecified"))
      (node (ref "P18") (pin "6") (pinfunction "GND_6") (pintype "unspecified"))
      (node (ref "P19") (pin "4") (pinfunction "4_4") (pintype "unspecified"))
      (node (ref "P20") (pin "1") (pinfunction "1_1") (pintype "unspecified"))
      (node (ref "P4") (pin "1") (pinfunction "1_1") (pintype "unspecified"))
      (node (ref "P5") (pin "1") (pinfunction "1_1") (pintype "input"))
      (node (ref "P6") (pin "2") (pinfunction "2_2") (pintype "input"))
      (node (ref "P7") (pin "1") (pinfunction "1_1") (pintype "unspecified"))
      (node (ref "P8") (pin "2") (pinfunction "2_2") (pintype "input"))
      (node (ref "P9") (pin "1") (pinfunction "1_1") (pintype "unspecified"))
      (node (ref "R10") (pin "1") (pinfunction "1_1") (pintype "unspecified"))
      (node (ref "R11") (pin "1") (pinfunction "1_1") (pintype "unspecified"))
      (node (ref "R13") (pin "2") (pinfunction "2_2") (pintype "unspecified"))
      (node (ref "R44") (pin "1") (pinfunction "1_1") (pintype "unspecified"))
      (node (ref "U12") (pin "15") (pinfunction "GND_15") (pintype "unspecified"))
      (node (ref "U13") (pin "3") (pinfunction "GND_3") (pintype "unspecified"))
      (node (ref "U14") (pin "3") (pinfunction "GND_3") (pintype "unspecified"))
      (node (ref "U15") (pin "3") (pinfunction "GND_3") (pintype "unspecified"))
      (node (ref "U17") (pin "1") (pinfunction "GND_1") (pintype "unspecified"))
      (node (ref "U3") (pin "1") (pinfunction "GND_1") (pintype "unspecified"))
      (node (ref "U5") (pin "23") (pinfunction "VSS_1_23") (pintype "unspecified"))
      (node (ref "U5") (pin "35") (pinfunction "VSS_2_35") (pintype "unspecified"))
      (node (ref "U5") (pin "47") (pinfunction "VSS_3_47") (pintype "unspecified"))
      (node (ref "U5") (pin "8") (pinfunction "VSSA_8") (pintype "unspecified"))
      (node (ref "U6") (pin "5") (pinfunction "GND_5") (pintype "input"))
      (node (ref "U6") (pin "6") (pinfunction "GND_6") (pintype "input"))
      (node (ref "U6") (pin "7") (pinfunction "GND_7") (pintype "input"))
      (node (ref "U6") (pin "8") (pinfunction "GND_8") (pintype "input"))
    )
    (net (code "60") (name "Net-(D6-Pad1)") (class "Default")
      (node (ref "D6") (pin "1") (pinfunction "1_1") (pintype "unspecified"))
      (node (ref "R4") (pin "2") (pinfunction "2_2") (pintype "unspecified"))
    )
    (net (code "61") (name "Net-(D7-Pad1)") (class "Default")
      (node (ref "D7") (pin "1") (pinfunction "1_1") (pintype "unspecified"))
      (node (ref "R7") (pin "1") (pinfunction "1_1") (pintype "unspecified"))
    )
    (net (code "62") (name "Net-(D8-A)") (class "Default")
      (node (ref "D8") (pin "2") (pinfunction "A_2") (pintype "input"))
      (node (ref "U17") (pin "3") (pinfunction "RXD_3") (pintype "unspecified"))
    )
    (net (code "63") (name "Net-(D9-Pad1)") (class "Default")
      (node (ref "D9") (pin "1") (pinfunction "1_1") (pintype "unspecified"))
      (node (ref "R8") (pin "1") (pinfunction "1_1") (pintype "unspecified"))
    )
    (net (code "64") (name "Net-(D10-Pad1)") (class "Default")
      (node (ref "D10") (pin "1") (pinfunction "1_1") (pintype "unspecified"))
      (node (ref "R9") (pin "1") (pinfunction "1_1") (pintype "unspecified"))
    )
    (net (code "65") (name "Net-(D14-Pad1)") (class "Default")
      (node (ref "D14") (pin "1") (pinfunction "1_1") (pintype "unspecified"))
      (node (ref "R14") (pin "1") (pinfunction "1_1") (pintype "unspecified"))
    )
    (net (code "66") (name "Net-(D15-Pad1)") (class "Default")
      (node (ref "D15") (pin "1") (pinfunction "1_1") (pintype "unspecified"))
      (node (ref "R15") (pin "1") (pinfunction "1_1") (pintype "unspecified"))
    )
    (net (code "67") (name "Net-(D17-c)") (class "Default")
      (node (ref "D17") (pin "1") (pinfunction "c_1") (pintype "input"))
      (node (ref "U17") (pin "2") (pinfunction "TXD_2") (pintype "unspecified"))
    )
    (net (code "68") (name "Net-(U6-ON{slash}OFF)") (class "Default")
      (node (ref "R13") (pin "1") (pinfunction "1_1") (pintype "unspecified"))
      (node (ref "U6") (pin "4") (pinfunction "ON/OFF_4") (pintype "input"))
    )
    (net (code "69") (name "Net-(U6-OUTPUT)") (class "Default")
      (node (ref "D11") (pin "2") (pinfunction "2_2") (pintype "input"))
      (node (ref "L1") (pin "2") (pinfunction "2_2") (pintype "unspecified"))
      (node (ref "U6") (pin "2") (pinfunction "OUTPUT_2") (pintype "input"))
    )
    (net (code "70") (name "Net-(U12-C1+)") (class "Default")
      (node (ref "C28") (pin "2") (pinfunction "2_2") (pintype "unspecified"))
      (node (ref "U12") (pin "1") (pinfunction "C1+_1") (pintype "unspecified"))
    )
    (net (code "71") (name "Net-(U12-C1-)") (class "Default")
      (node (ref "C28") (pin "1") (pinfunction "1_1") (pintype "unspecified"))
      (node (ref "U12") (pin "3") (pinfunction "C1-_3") (pintype "unspecified"))
    )
    (net (code "72") (name "Net-(U12-C2+)") (class "Default")
      (node (ref "C30") (pin "2") (pinfunction "2_2") (pintype "unspecified"))
      (node (ref "U12") (pin "4") (pinfunction "C2+_4") (pintype "unspecified"))
    )
    (net (code "73") (name "Net-(U12-C2-)") (class "Default")
      (node (ref "C30") (pin "1") (pinfunction "1_1") (pintype "unspecified"))
      (node (ref "U12") (pin "5") (pinfunction "C2-_5") (pintype "unspecified"))
    )
    (net (code "74") (name "Net-(U12-V+)") (class "Default")
      (node (ref "C27") (pin "2") (pinfunction "2_2") (pintype "unspecified"))
      (node (ref "U12") (pin "2") (pinfunction "V+_2") (pintype "unspecified"))
    )
    (net (code "75") (name "Net-(U12-V-)") (class "Default")
      (node (ref "C31") (pin "1") (pinfunction "1_1") (pintype "unspecified"))
      (node (ref "U12") (pin "6") (pinfunction "V-_6") (pintype "unspecified"))
    )
    (net (code "76") (name "Net-(U17-DTR#)") (class "Default")
      (node (ref "C7") (pin "1") (pinfunction "1_1") (pintype "unspecified"))
      (node (ref "U17") (pin "13") (pinfunction "DTR#_13") (pintype "unspecified"))
    )
    (net (code "77") (name "Net-(U17-V3)") (class "Default")
      (node (ref "C25") (pin "1") (pinfunction "1_1") (pintype "unspecified"))
      (node (ref "U17") (pin "4") (pinfunction "V3_4") (pintype "unspecified"))
    )
    (net (code "78") (name "Net-(U17-XI)") (class "Default")
      (node (ref "C26") (pin "1") (pinfunction "1_1") (pintype "unspecified"))
      (node (ref "U17") (pin "7") (pinfunction "XI_7") (pintype "unspecified"))
      (node (ref "Y1") (pin "2") (pinfunction "OSC2_2") (pintype "unspecified"))
    )
    (net (code "79") (name "Net-(U17-XO)") (class "Default")
      (node (ref "C36") (pin "1") (pinfunction "1_1") (pintype "unspecified"))
      (node (ref "U17") (pin "8") (pinfunction "XO_8") (pintype "unspecified"))
      (node (ref "Y1") (pin "1") (pinfunction "OSC1_1") (pintype "unspecified"))
    )
    (net (code "80") (name "VIN_24V") (class "Default")
      (node (ref "C21") (pin "2") (pinfunction "2_2") (pintype "unspecified"))
      (node (ref "C22") (pin "1") (pintype "unspecified"))
      (node (ref "D13") (pin "2") (pinfunction "2_2") (pintype "unspecified"))
      (node (ref "U6") (pin "1") (pinfunction "VIN_1") (pintype "input"))
    )
    (net (code "81") (name "VUSB") (class "Default")
      (node (ref "H11") (pin "2") (pinfunction "2_2") (pintype "unspecified"))
      (node (ref "P18") (pin "1") (pinfunction "VBUS_1") (pintype "unspecified"))
    )
    (net (code "82") (name "unconnected-(DB1-MH1-Pad10)") (class "Default")
      (node (ref "DB1") (pin "10") (pinfunction "MH1_10") (pintype "input"))
    )
    (net (code "83") (name "unconnected-(DB1-MH2-Pad11)") (class "Default")
      (node (ref "DB1") (pin "11") (pinfunction "MH2_11") (pintype "input"))
    )
    (net (code "84") (name "unconnected-(DB1-Pad7)") (class "Default")
      (node (ref "DB1") (pin "7") (pinfunction "7_7") (pintype "input"))
    )
    (net (code "85") (name "unconnected-(U5-VBAT-Pad1)") (class "Default")
      (node (ref "U5") (pin "1") (pinfunction "VBAT_1") (pintype "unspecified"))
    )
    (net (code "86") (name "unconnected-(U12-R2OUT-Pad9)") (class "Default")
      (node (ref "U12") (pin "9") (pinfunction "R2OUT_9") (pintype "unspecified"))
    )
    (net (code "87") (name "unconnected-(U12-T2IN-Pad10)") (class "Default")
      (node (ref "U12") (pin "10") (pinfunction "T2IN_10") (pintype "unspecified"))
    )
    (net (code "88") (name "unconnected-(U13-NC-Pad1)") (class "Default")
      (node (ref "U13") (pin "1") (pinfunction "NC_1") (pintype "unspecified"))
    )
    (net (code "89") (name "unconnected-(U14-NC-Pad1)") (class "Default")
      (node (ref "U14") (pin "1") (pinfunction "NC_1") (pintype "unspecified"))
    )
    (net (code "90") (name "unconnected-(U15-NC-Pad1)") (class "Default")
      (node (ref "U15") (pin "1") (pinfunction "NC_1") (pintype "unspecified"))
    )
    (net (code "91") (name "unconnected-(U17-CTS#-Pad9)") (class "Default")
      (node (ref "U17") (pin "9") (pinfunction "CTS#_9") (pintype "unspecified"))
    )
    (net (code "92") (name "unconnected-(U17-DCD#-Pad12)") (class "Default")
      (node (ref "U17") (pin "12") (pinfunction "DCD#_12") (pintype "unspecified"))
    )
    (net (code "93") (name "unconnected-(U17-DSR#-Pad10)") (class "Default")
      (node (ref "U17") (pin "10") (pinfunction "DSR#_10") (pintype "unspecified"))
    )
    (net (code "94") (name "unconnected-(U17-R232-Pad15)") (class "Default")
      (node (ref "U17") (pin "15") (pinfunction "R232_15") (pintype "unspecified"))
    )
    (net (code "95") (name "unconnected-(U17-RI#-Pad11)") (class "Default")
      (node (ref "U17") (pin "11") (pinfunction "RI#_11") (pintype "unspecified"))
    )
    (net (code "96") (name "unconnected-(U17-RTS#-Pad14)") (class "Default")
      (node (ref "U17") (pin "14") (pinfunction "RTS#_14") (pintype "unspecified"))
    )
  )
)
